# IO4-CMRI-Interface.net
KiCad netlist of a schematic drawn in EAGLE
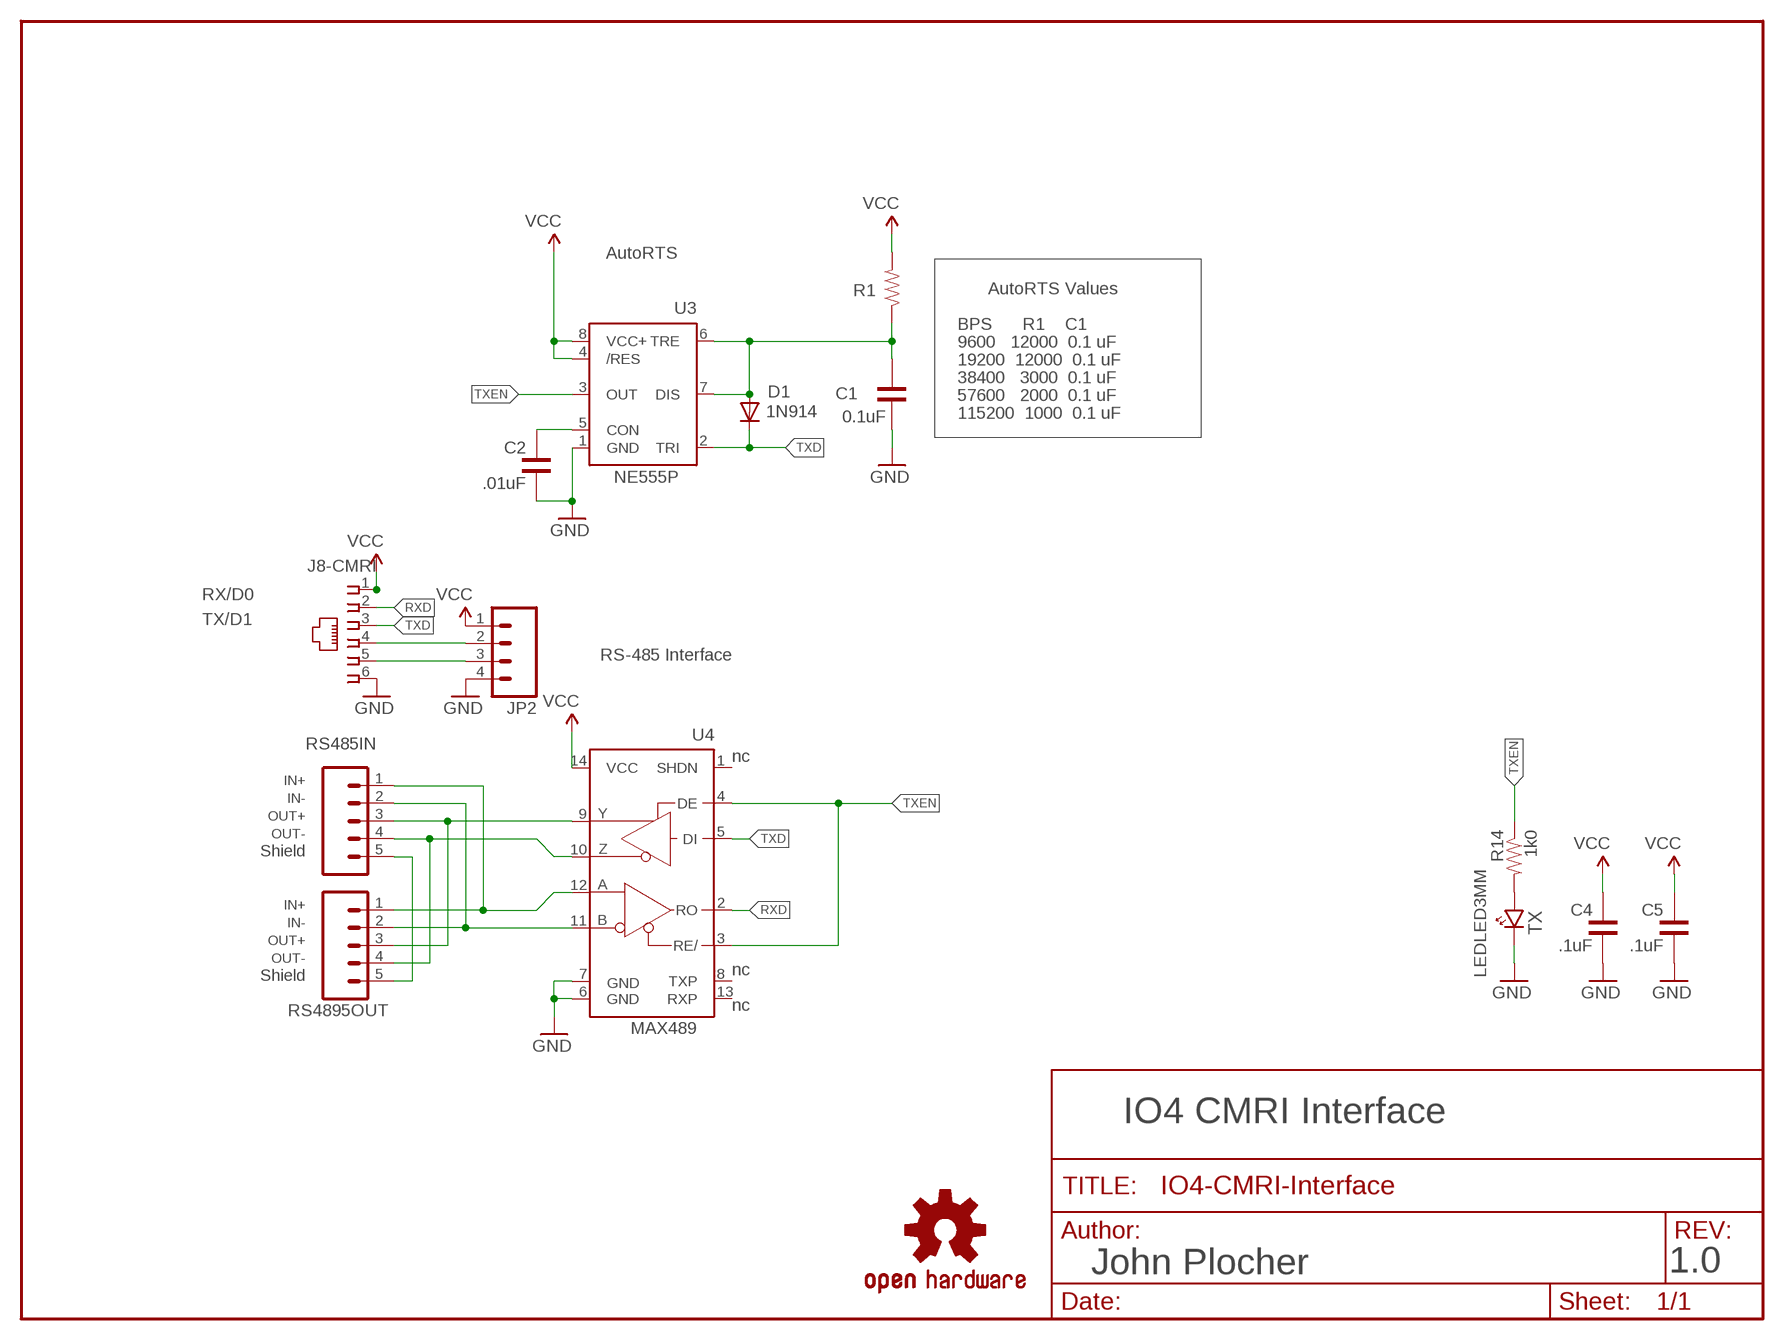
[diagram p0: schematic, sheet 1]

(export (version "E")
  (design (tool "Eeschema 10.0.6"))
  (components
    (comp (ref "C1")
      (value "0.1uF")
      (footprint "eagle-import:CAP-PTH-SMALL")
      (libsource (lib "eagle-import") (part "CPTH"))
    )
    (comp (ref "C2")
      (value ".01uF")
      (footprint "eagle-import:CAP-PTH-SMALL")
      (libsource (lib "eagle-import") (part "CPTH"))
    )
    (comp (ref "C4")
      (value ".1uF")
      (footprint "eagle-import:CAP-PTH-SMALL")
      (libsource (lib "eagle-import") (part "CPTH"))
    )
    (comp (ref "C5")
      (value ".1uF")
      (footprint "eagle-import:CAP-PTH-SMALL")
      (libsource (lib "eagle-import") (part "CPTH"))
    )
    (comp (ref "D1")
      (value "1N914")
      (footprint "eagle-import:DIODE-1N4001")
      (libsource (lib "eagle-import") (part "DIODEPTH"))
    )
    (comp (ref "J8-CMRI")
      (value "RJ12CORCOM")
      (footprint "eagle-import:RJ11-NO_SHIELD")
      (libsource (lib "eagle-import") (part "RJ12CORCOM"))
    )
    (comp (ref "JP2")
      (value "M04SCREW_LOCK")
      (footprint "eagle-import:SCREWTERMINAL-3.5MM-4_LOCK")
      (libsource (lib "eagle-import") (part "M04SCREW_LOCK"))
    )
    (comp (ref "R1")
      (value "RPTH-1/6W")
      (footprint "eagle-import:1_6W-RES")
      (libsource (lib "eagle-import") (part "RPTH-1/6W"))
    )
    (comp (ref "R14")
      (value "1k0")
      (footprint "eagle-import:1_6W-RES")
      (libsource (lib "eagle-import") (part "RPTH-1/6W"))
    )
    (comp (ref "RS485IN")
      (value "M05PTH")
      (footprint "eagle-import:1X05")
      (libsource (lib "eagle-import") (part "M05PTH"))
    )
    (comp (ref "RS4895OUT")
      (value "M05LOCK")
      (footprint "eagle-import:1X05_LOCK")
      (libsource (lib "eagle-import") (part "M05LOCK"))
    )
    (comp (ref "TX")
      (value "LEDLED3MM")
      (footprint "eagle-import:LED3MM")
      (libsource (lib "eagle-import") (part "LEDLED3MM"))
    )
    (comp (ref "U$1")
      (value "OSHW-LOGOL")
      (footprint "eagle-import:OSHW-LOGO-L")
      (libsource (lib "eagle-import") (part "OSHW-LOGOL"))
    )
    (comp (ref "U3")
      (value "NE555P")
      (footprint "eagle-import:DIL-08")
      (fields (field (name "MF") "Arrow Electronics") (field (name "MPN") "NE555N"))
      (libsource (lib "eagle-import") (part "NE555P"))
    )
    (comp (ref "U4")
      (value "MAX3465CPD")
      (footprint "eagle-import:DIL14")
      (fields (field (name "MPN") "MAX3465CPD+"))
      (libsource (lib "eagle-import") (part "MAX346PD5C"))
    )
  )
  (nets
    (net (code "1") (name "GND") (class "Default")
      (node (ref "C1") (pin "2") (pinfunction "2_2") (pintype "passive"))
      (node (ref "C2") (pin "2") (pinfunction "2_2") (pintype "passive"))
      (node (ref "C4") (pin "2") (pinfunction "2_2") (pintype "passive"))
      (node (ref "C5") (pin "2") (pinfunction "2_2") (pintype "passive"))
      (node (ref "J8-CMRI") (pin "6") (pinfunction "6_6") (pintype "passive"))
      (node (ref "JP2") (pin "4") (pinfunction "4_4") (pintype "passive"))
      (node (ref "TX") (pin "K") (pinfunction "C_K") (pintype "passive"))
      (node (ref "U3") (pin "1") (pinfunction "GND_1") (pintype "power_in"))
      (node (ref "U4") (pin "6") (pinfunction "GND_6") (pintype "power_in"))
      (node (ref "U4") (pin "7") (pinfunction "GND_7") (pintype "power_in"))
    )
    (net (code "2") (name "Net-(J8-CMRI-Pad4)") (class "Default")
      (node (ref "J8-CMRI") (pin "4") (pinfunction "4_4") (pintype "passive"))
      (node (ref "JP2") (pin "2") (pinfunction "2_2") (pintype "passive"))
    )
    (net (code "3") (name "Net-(J8-CMRI-Pad5)") (class "Default")
      (node (ref "J8-CMRI") (pin "5") (pinfunction "5_5") (pintype "passive"))
      (node (ref "JP2") (pin "3") (pinfunction "3_3") (pintype "passive"))
    )
    (net (code "4") (name "Net-(R14-Pad2)") (class "Default")
      (node (ref "R14") (pin "2") (pinfunction "2_2") (pintype "passive"))
      (node (ref "TX") (pin "A") (pinfunction "A_A") (pintype "passive"))
    )
    (net (code "5") (name "Net-(RS485IN-Pad5)") (class "Default")
      (node (ref "RS485IN") (pin "5") (pinfunction "5_5") (pintype "passive"))
      (node (ref "RS4895OUT") (pin "5") (pinfunction "5_5") (pintype "passive"))
    )
    (net (code "6") (name "Net-(U3-CON)") (class "Default")
      (node (ref "C2") (pin "1") (pinfunction "1_1") (pintype "passive"))
      (node (ref "U3") (pin "5") (pinfunction "CON_5") (pintype "input"))
    )
    (net (code "7") (name "Net-(U3-DIS)") (class "Default")
      (node (ref "C1") (pin "1") (pinfunction "1_1") (pintype "passive"))
      (node (ref "D1") (pin "A") (pinfunction "A_A") (pintype "passive"))
      (node (ref "R1") (pin "1") (pinfunction "1_1") (pintype "passive"))
      (node (ref "U3") (pin "6") (pinfunction "TRE_6") (pintype "input"))
      (node (ref "U3") (pin "7") (pinfunction "DIS_7") (pintype "input"))
    )
    (net (code "8") (name "Net-(U4-A)") (class "Default")
      (node (ref "RS485IN") (pin "1") (pinfunction "1_1") (pintype "passive"))
      (node (ref "RS4895OUT") (pin "1") (pinfunction "1_1") (pintype "passive"))
      (node (ref "U4") (pin "12") (pinfunction "A_12") (pintype "input"))
    )
    (net (code "9") (name "Net-(U4-B)") (class "Default")
      (node (ref "RS485IN") (pin "2") (pinfunction "2_2") (pintype "passive"))
      (node (ref "RS4895OUT") (pin "2") (pinfunction "2_2") (pintype "passive"))
      (node (ref "U4") (pin "11") (pinfunction "B_11") (pintype "input"))
    )
    (net (code "10") (name "Net-(U4-Y)") (class "Default")
      (node (ref "RS485IN") (pin "3") (pinfunction "3_3") (pintype "passive"))
      (node (ref "RS4895OUT") (pin "3") (pinfunction "3_3") (pintype "passive"))
      (node (ref "U4") (pin "9") (pinfunction "Y_9") (pintype "output"))
    )
    (net (code "11") (name "Net-(U4-Z)") (class "Default")
      (node (ref "RS485IN") (pin "4") (pinfunction "4_4") (pintype "passive"))
      (node (ref "RS4895OUT") (pin "4") (pinfunction "4_4") (pintype "passive"))
      (node (ref "U4") (pin "10") (pinfunction "Z_10") (pintype "output"))
    )
    (net (code "12") (name "RXD") (class "Default")
      (node (ref "J8-CMRI") (pin "2") (pinfunction "2_2") (pintype "passive"))
      (node (ref "U4") (pin "2") (pinfunction "RO_2") (pintype "output"))
    )
    (net (code "13") (name "TXD") (class "Default")
      (node (ref "D1") (pin "C") (pinfunction "C_C") (pintype "passive"))
      (node (ref "J8-CMRI") (pin "3") (pinfunction "3_3") (pintype "passive"))
      (node (ref "U3") (pin "2") (pinfunction "TRI_2") (pintype "input"))
      (node (ref "U4") (pin "5") (pinfunction "DI_5") (pintype "input"))
    )
    (net (code "14") (name "TXEN") (class "Default")
      (node (ref "R14") (pin "1") (pinfunction "1_1") (pintype "passive"))
      (node (ref "U3") (pin "3") (pinfunction "OUT_3") (pintype "output"))
      (node (ref "U4") (pin "3") (pinfunction "RE/_3") (pintype "input"))
      (node (ref "U4") (pin "4") (pinfunction "DE_4") (pintype "input"))
    )
    (net (code "15") (name "VCC") (class "Default")
      (node (ref "C4") (pin "1") (pinfunction "1_1") (pintype "passive"))
      (node (ref "C5") (pin "1") (pinfunction "1_1") (pintype "passive"))
      (node (ref "J8-CMRI") (pin "1") (pinfunction "1_1") (pintype "passive"))
      (node (ref "JP2") (pin "1") (pinfunction "1_1") (pintype "passive"))
      (node (ref "R1") (pin "2") (pinfunction "2_2") (pintype "passive"))
      (node (ref "U3") (pin "4") (pinfunction "/RES_4") (pintype "input"))
      (node (ref "U3") (pin "8") (pinfunction "VCC+_8") (pintype "power_in"))
      (node (ref "U4") (pin "14") (pinfunction "VCC_14") (pintype "power_in"))
    )
    (net (code "16") (name "unconnected-(U4-RXP-Pad13)") (class "Default")
      (node (ref "U4") (pin "13") (pinfunction "RXP_13") (pintype "passive"))
    )
    (net (code "17") (name "unconnected-(U4-SHDN-Pad1)") (class "Default")
      (node (ref "U4") (pin "1") (pinfunction "SHDN_1") (pintype "input"))
    )
    (net (code "18") (name "unconnected-(U4-TXP-Pad8)") (class "Default")
      (node (ref "U4") (pin "8") (pinfunction "TXP_8") (pintype "passive"))
    )
  )
)
